# input.net
KiCad netlist of a schematic drawn in Altium Designer
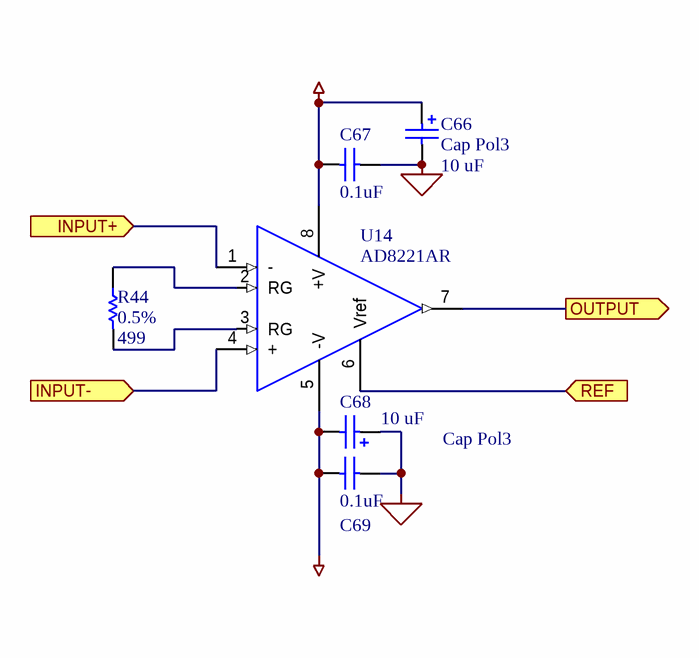
[diagram p0: input.SCHDOC]

(export (version "E")
  (design (tool "Eeschema 10.0.6"))
  (components
    (comp (ref "C66")
      (value "Cap Pol3")
      (footprint "TC3216-1206")
      (description "Polarized Capacitor (Surface Mount)")
      (fields
        (field (name "MANUFACTURER") "Generic Components")
        (field (name "ALTIUM_VALUE") "10 uF")
        (field (name "PUBLISHER") "Altium Limited")
      )
      (libsource (lib "Miscellaneous Devices") (part "Cap Pol3"))
    )
    (comp (ref "C67")
      (value "0.1uF")
      (footprint "CC1608-0603")
      (description "Capacitor")
      (fields
        (field (name "MANUFACTURER") "Generic Components")
        (field (name "Comment") "Cap")
        (field (name "PUBLISHER") "Altium Limited")
      )
      (libsource (lib "Miscellaneous Devices") (part "Cap"))
    )
    (comp (ref "C68")
      (value "Cap Pol3")
      (footprint "TC3216-1206")
      (description "Polarized Capacitor (Surface Mount)")
      (fields
        (field (name "MANUFACTURER") "Generic Components")
        (field (name "ALTIUM_VALUE") "10 uF")
        (field (name "PUBLISHER") "Altium Limited")
      )
      (libsource (lib "Miscellaneous Devices") (part "Cap Pol3"))
    )
    (comp (ref "C69")
      (value "0.1uF")
      (footprint "CC1608-0603")
      (description "Capacitor")
      (fields
        (field (name "MANUFACTURER") "Generic Components")
        (field (name "Comment") "Cap")
        (field (name "PUBLISHER") "Altium Limited")
      )
      (libsource (lib "Miscellaneous Devices") (part "Cap"))
    )
    (comp (ref "R44")
      (value "0.5%")
      (footprint "R2012-0805")
      (description "RR1220P-4990-D-M")
      (fields
        (field (name "MANUFACTURER") "Generic Components")
        (field (name "ALTIUM_VALUE") "499")
        (field (name "PUBLISHER") "Altium Limited")
      )
      (libsource (lib "Miscellaneous Devices") (part "Res1"))
    )
    (comp (ref "U14")
      (value "AD8221AR")
      (footprint "SO-G8")
      (description "AD8221 Precision Instrumentation Amplifier")
      (libsource (lib "My devices") (part "AD8221"))
    )
  )
  (nets
    (net (code "1") (name "/INPUT+") (class "Default")
      (node (ref "U14") (pin "1") (pinfunction "-_1") (pintype "input"))
    )
    (net (code "2") (name "/INPUT-") (class "Default")
      (node (ref "U14") (pin "4") (pinfunction "+_4") (pintype "input"))
    )
    (net (code "3") (name "/OUTPUT") (class "Default")
      (node (ref "U14") (pin "7") (pinfunction "Vout_7") (pintype "output"))
    )
    (net (code "4") (name "/REF") (class "Default")
      (node (ref "U14") (pin "6") (pinfunction "Vref_6") (pintype "passive"))
    )
    (net (code "5") (name "AGND") (class "Default")
      (node (ref "C66") (pin "2") (pinfunction "2_2") (pintype "passive"))
      (node (ref "C67") (pin "2") (pinfunction "2_2") (pintype "passive"))
      (node (ref "C68") (pin "1") (pinfunction "1_1") (pintype "passive"))
      (node (ref "C69") (pin "2") (pinfunction "2_2") (pintype "passive"))
    )
    (net (code "6") (name "AVDD") (class "Default")
      (node (ref "C66") (pin "1") (pinfunction "1_1") (pintype "passive"))
      (node (ref "C67") (pin "1") (pinfunction "1_1") (pintype "passive"))
      (node (ref "U14") (pin "8") (pinfunction "+V_8") (pintype "power_in"))
    )
    (net (code "7") (name "AVSS") (class "Default")
      (node (ref "C68") (pin "2") (pinfunction "2_2") (pintype "passive"))
      (node (ref "C69") (pin "1") (pinfunction "1_1") (pintype "passive"))
      (node (ref "U14") (pin "5") (pinfunction "-V_5") (pintype "power_in"))
    )
    (net (code "8") (name "Net-(R44-Pad1)") (class "Default")
      (node (ref "R44") (pin "1") (pinfunction "1_1") (pintype "passive"))
      (node (ref "U14") (pin "2") (pinfunction "RG_2") (pintype "input"))
    )
    (net (code "9") (name "Net-(R44-Pad2)") (class "Default")
      (node (ref "R44") (pin "2") (pinfunction "2_2") (pintype "passive"))
      (node (ref "U14") (pin "3") (pinfunction "RG_3") (pintype "input"))
    )
  )
)
